# Sheet3.net
KiCad netlist of a schematic drawn in Altium Designer
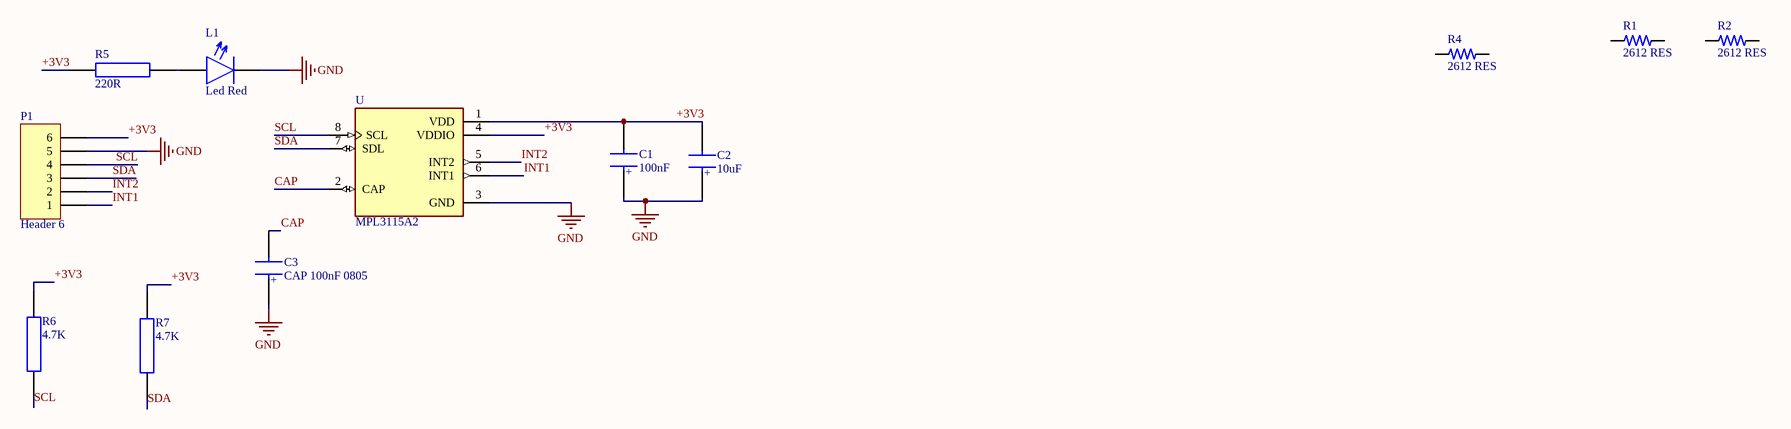
[diagram p0: Sheet3.SchDoc]

(export (version "E")
  (design (tool "Eeschema 10.0.6"))
  (components
    (comp (ref "C1")
      (value "100nF")
      (footprint "CAP_805")
      (description "0805 smd")
      (libsource (lib "Udemy_Schlib1") (part "CAP 100nF 0805"))
    )
    (comp (ref "C2")
      (value "10uF")
      (footprint "CAP_805")
      (description "0805 smd")
      (libsource (lib "Udemy_Schlib1") (part "CAP 100nF 0805"))
    )
    (comp (ref "C3")
      (value "CAP 100nF 0805")
      (footprint "CAP_805")
      (description "0805 smd")
      (libsource (lib "Udemy_Schlib1") (part "CAP 100nF 0805"))
    )
    (comp (ref "L1")
      (value "Led Red")
      (footprint "Led 1206")
      (libsource (lib "Udemy_Schlib1") (part "Led Red"))
    )
    (comp (ref "P1")
      (value "Header 6")
      (footprint "HDR1X6")
      (description "Header, 6-Pin")
      (fields (field (name "PUBLISHER") "Altium Limited"))
      (libsource (lib "Miscellaneous Connectors") (part "Header 6"))
    )
    (comp (ref "R1")
      (value "2612 RES")
      (footprint "RESC6331X70N")
      (description "CRGV2512 1% 261K 1600V")
      (fields (field (name "MP") "6-1879539-9"))
      (libsource (lib "Schlib") (part "2612 RES"))
    )
    (comp (ref "R2")
      (value "2612 RES")
      (footprint "RESC6331X70N")
      (description "CRGV2512 1% 261K 1600V")
      (fields (field (name "MP") "6-1879539-9"))
      (libsource (lib "Schlib") (part "2612 RES"))
    )
    (comp (ref "R4")
      (value "2612 RES")
      (footprint "RESC6331X70N")
      (description "CRGV2512 1% 261K 1600V")
      (fields (field (name "MP") "6-1879539-9"))
      (libsource (lib "Schlib") (part "2612 RES"))
    )
    (comp (ref "R5")
      (value "220R")
      (footprint "RES_1206")
      (libsource (lib "Udemy_Schlib1") (part "RES 4.7K 1206"))
    )
    (comp (ref "R6")
      (value "4.7K")
      (footprint "RES_1206")
      (libsource (lib "Udemy_Schlib1") (part "RES 4.7K 1206"))
    )
    (comp (ref "R7")
      (value "4.7K")
      (footprint "RES_1206")
      (libsource (lib "Udemy_Schlib1") (part "RES 4.7K 1206"))
    )
    (comp (ref "U")
      (value "MPL3115A2")
      (footprint "PSON125P300X500X120-8N")
      (description "Pressure Sensor 7.25PSI ~ 15.95PSI _50kPa ~ 110kPa_ Absolute 24 b 8-TLGA")
      (fields (field (name "MF") "NXP USA"))
      (libsource (lib "Schlib") (part "MPL3115A2"))
    )
  )
  (nets
    (net (code "1") (name "/+3V3") (class "Default")
      (node (ref "C1") (pin "2") (pinfunction "2_2") (pintype "passive"))
      (node (ref "C2") (pin "2") (pinfunction "2_2") (pintype "passive"))
      (node (ref "P1") (pin "6") (pinfunction "6_6") (pintype "passive"))
      (node (ref "R5") (pin "2") (pintype "passive"))
      (node (ref "R6") (pin "2") (pintype "passive"))
      (node (ref "R7") (pin "2") (pintype "passive"))
      (node (ref "U") (pin "1") (pinfunction "VDD_1") (pintype "power_in"))
      (node (ref "U") (pin "4") (pinfunction "VDDIO_4") (pintype "power_in"))
    )
    (net (code "2") (name "/CAP") (class "Default")
      (node (ref "C3") (pin "2") (pinfunction "2_2") (pintype "passive"))
      (node (ref "U") (pin "2") (pinfunction "CAP_2") (pintype "bidirectional"))
    )
    (net (code "3") (name "/INT1") (class "Default")
      (node (ref "P1") (pin "1") (pinfunction "1_1") (pintype "passive"))
      (node (ref "U") (pin "6") (pinfunction "INT1_6") (pintype "output"))
    )
    (net (code "4") (name "/INT2") (class "Default")
      (node (ref "P1") (pin "2") (pinfunction "2_2") (pintype "passive"))
      (node (ref "U") (pin "5") (pinfunction "INT2_5") (pintype "output"))
    )
    (net (code "5") (name "/SCL") (class "Default")
      (node (ref "P1") (pin "4") (pinfunction "4_4") (pintype "passive"))
      (node (ref "R6") (pin "1") (pintype "passive"))
      (node (ref "U") (pin "8") (pinfunction "SCL_8") (pintype "input"))
    )
    (net (code "6") (name "/SDA") (class "Default")
      (node (ref "P1") (pin "3") (pinfunction "3_3") (pintype "passive"))
      (node (ref "R7") (pin "1") (pintype "passive"))
      (node (ref "U") (pin "7") (pinfunction "SDL_7") (pintype "bidirectional"))
    )
    (net (code "7") (name "GND") (class "Default")
      (node (ref "C1") (pin "1") (pinfunction "1_1") (pintype "passive"))
      (node (ref "C2") (pin "1") (pinfunction "1_1") (pintype "passive"))
      (node (ref "C3") (pin "1") (pinfunction "1_1") (pintype "passive"))
      (node (ref "L1") (pin "2") (pintype "passive"))
      (node (ref "P1") (pin "5") (pinfunction "5_5") (pintype "passive"))
      (node (ref "U") (pin "3") (pinfunction "GND_3") (pintype "power_in"))
    )
    (net (code "8") (name "Net-(L1-Pad1)") (class "Default")
      (node (ref "L1") (pin "1") (pintype "passive"))
      (node (ref "R5") (pin "1") (pintype "passive"))
    )
    (net (code "9") (name "unconnected-(R1-Pad1)") (class "Default")
      (node (ref "R1") (pin "1") (pinfunction "1_1") (pintype "passive"))
    )
    (net (code "10") (name "unconnected-(R1-Pad2)") (class "Default")
      (node (ref "R1") (pin "2") (pinfunction "2_2") (pintype "passive"))
    )
    (net (code "11") (name "unconnected-(R2-Pad1)") (class "Default")
      (node (ref "R2") (pin "1") (pinfunction "1_1") (pintype "passive"))
    )
    (net (code "12") (name "unconnected-(R2-Pad2)") (class "Default")
      (node (ref "R2") (pin "2") (pinfunction "2_2") (pintype "passive"))
    )
    (net (code "13") (name "unconnected-(R4-Pad1)") (class "Default")
      (node (ref "R4") (pin "1") (pinfunction "1_1") (pintype "passive"))
    )
    (net (code "14") (name "unconnected-(R4-Pad2)") (class "Default")
      (node (ref "R4") (pin "2") (pinfunction "2_2") (pintype "passive"))
    )
  )
)
